# ABL_Covid_Test_UI_Module.net
KiCad netlist of a schematic drawn in EasyEDA
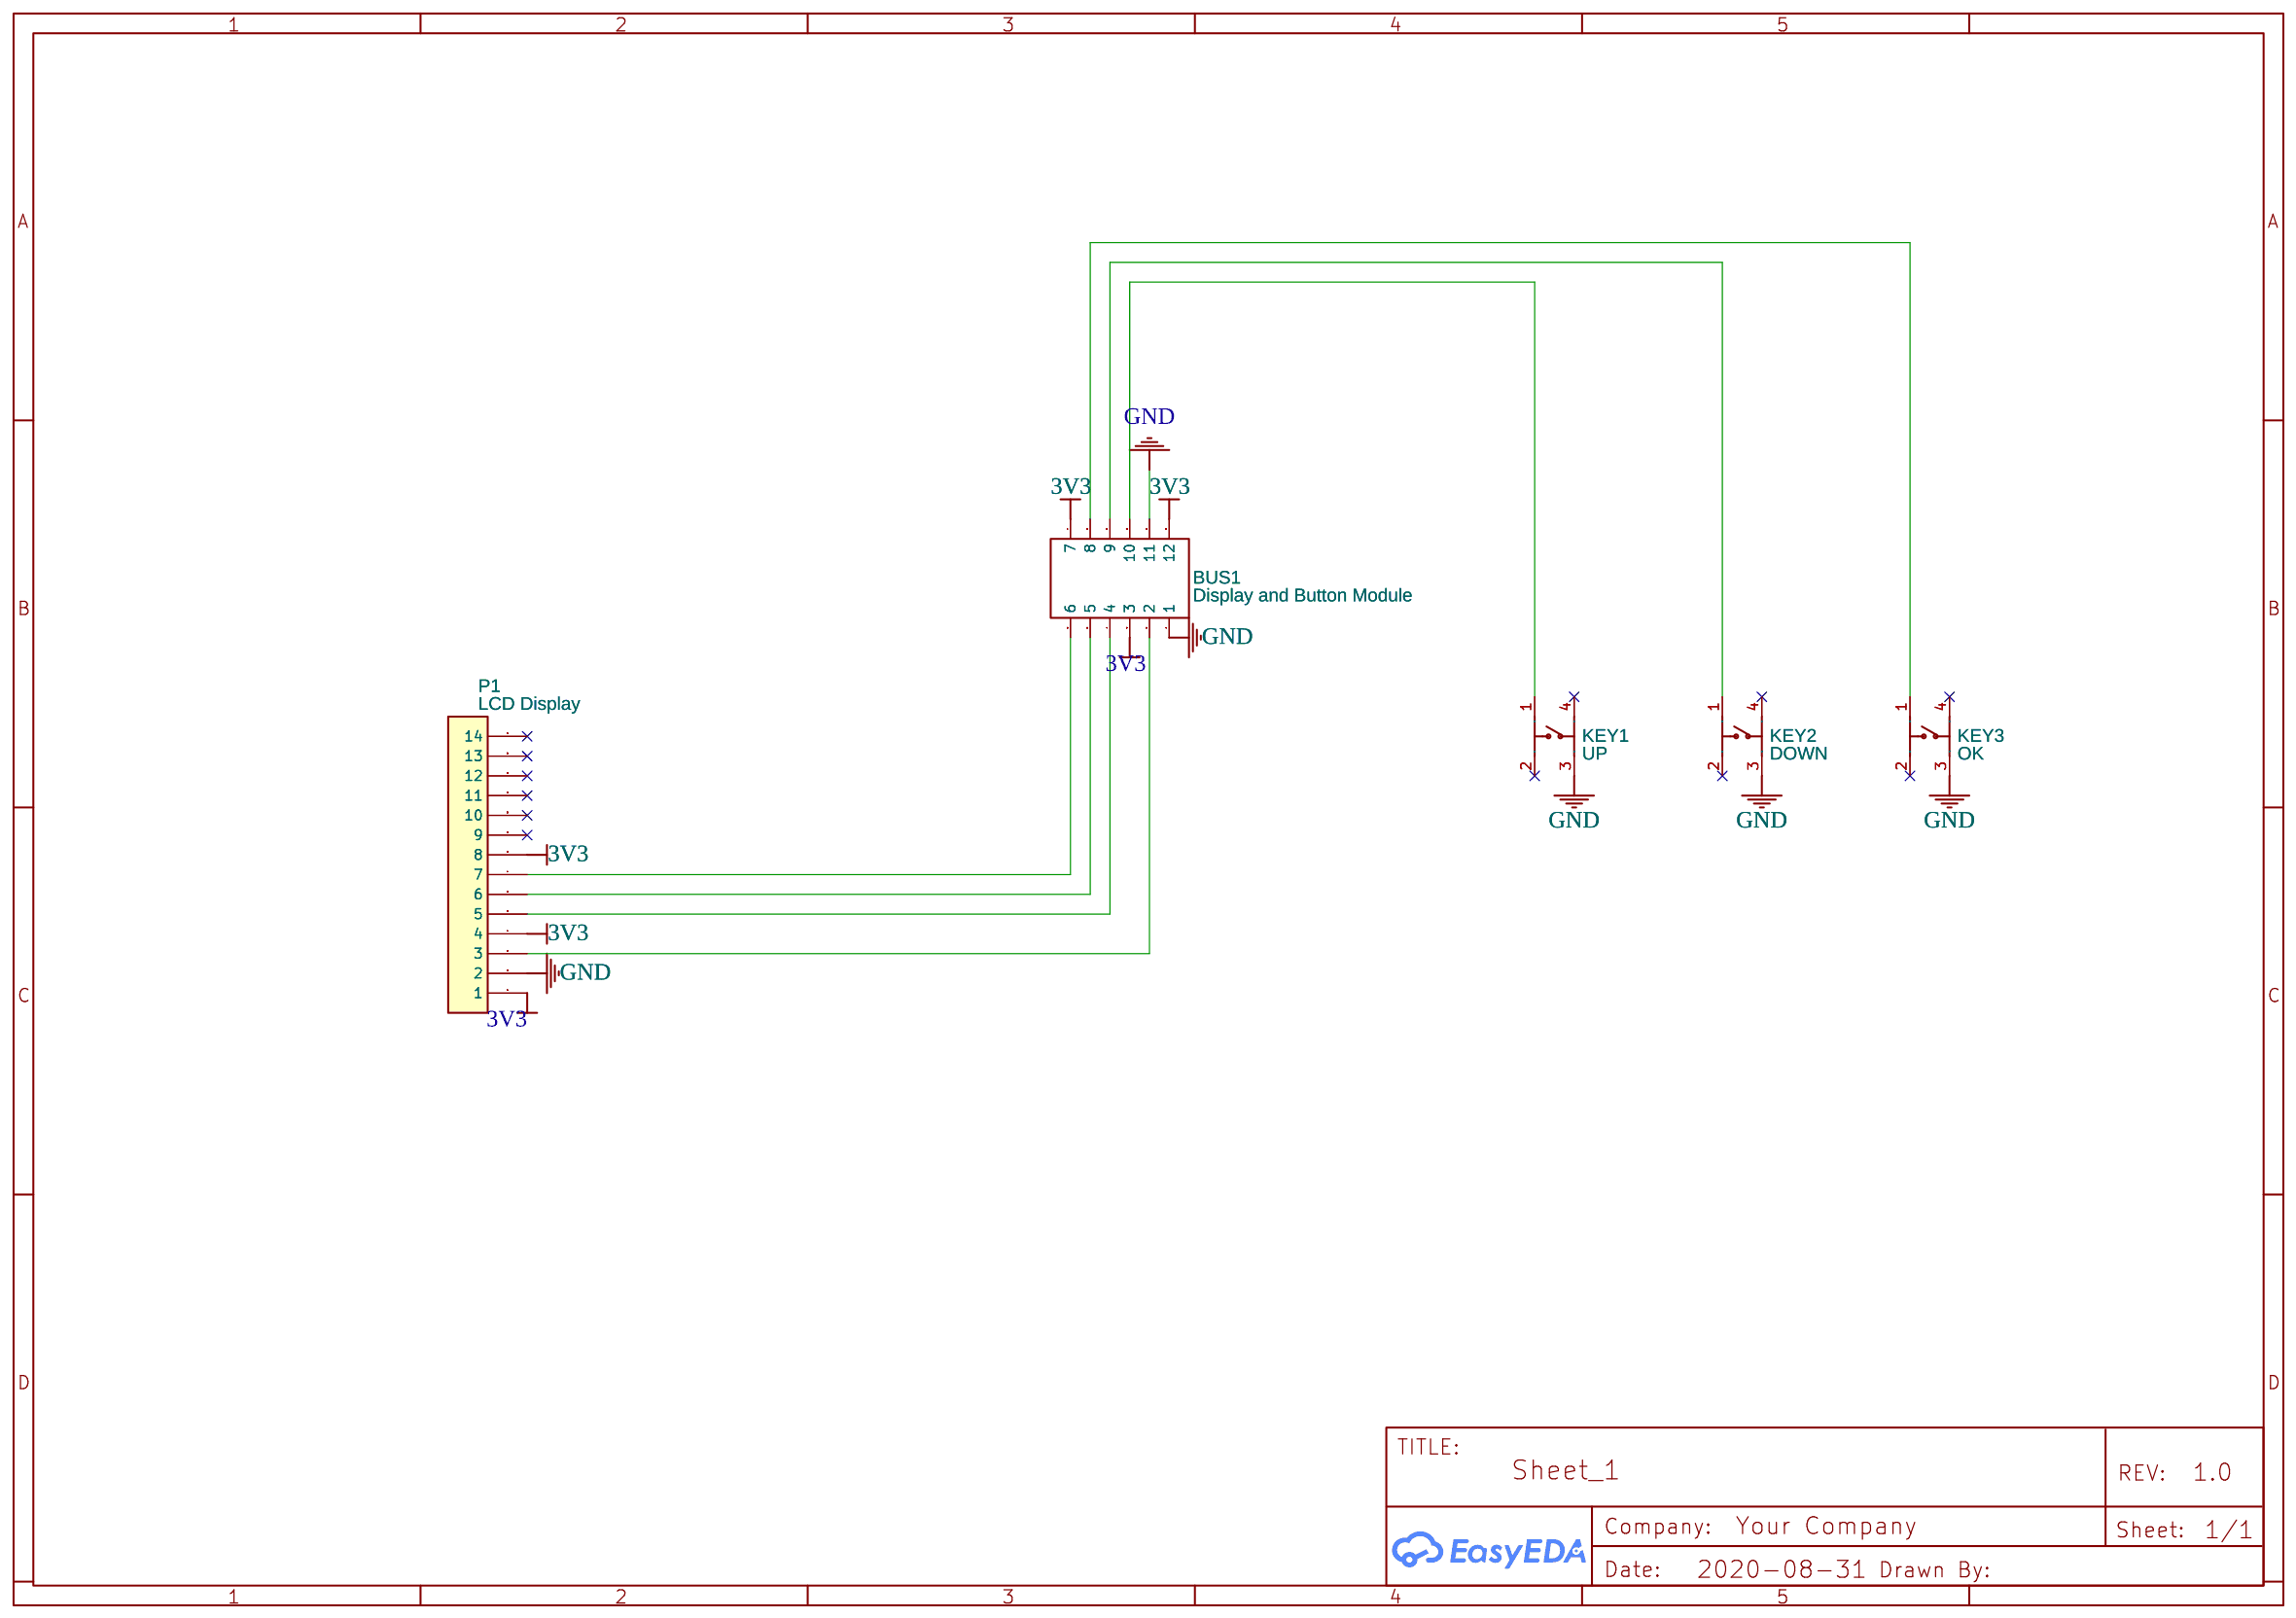
[diagram p0: schematic sheet]

(export (version "E")
  (design (tool "Eeschema 10.0.6"))
  (components
    (comp (ref "BUS1") (value "Display and Button Module") (libsource (lib "") (part "12p 2x6 header")))
    (comp (ref "KEY1")
      (value "UP")
      (fields
        (field (name "BOM_Manufacturer Part") "button6*6*8")
        (field (name "BOM_Supplier Part") "C59982")
      )
      (libsource (lib "") (part "button6*6*8"))
    )
    (comp (ref "KEY2")
      (value "DOWN")
      (fields
        (field (name "BOM_Manufacturer Part") "button6*6*8")
        (field (name "BOM_Supplier Part") "C59982")
      )
      (libsource (lib "") (part "button6*6*8"))
    )
    (comp (ref "KEY3")
      (value "OK")
      (fields
        (field (name "BOM_Manufacturer Part") "button6*6*8")
        (field (name "BOM_Supplier Part") "C59982")
      )
      (libsource (lib "") (part "button6*6*8"))
    )
    (comp (ref "P1") (value "LCD Display") (libsource (lib "") (part "HEADER 14X1")))
  )
  (nets
    (net (code "1") (name "3V3") (class "Default")
      (node (ref "BUS1") (pin "12") (pinfunction "12_12") (pintype "unspecified"))
      (node (ref "BUS1") (pin "3") (pinfunction "3_3") (pintype "unspecified"))
      (node (ref "BUS1") (pin "7") (pinfunction "7_7") (pintype "unspecified"))
      (node (ref "P1") (pin "1") (pinfunction "1_1") (pintype "unspecified"))
      (node (ref "P1") (pin "4") (pinfunction "4_4") (pintype "unspecified"))
      (node (ref "P1") (pin "8") (pinfunction "8_8") (pintype "unspecified"))
    )
    (net (code "2") (name "GND") (class "Default")
      (node (ref "BUS1") (pin "1") (pinfunction "1_1") (pintype "unspecified"))
      (node (ref "BUS1") (pin "11") (pinfunction "11_11") (pintype "unspecified"))
      (node (ref "KEY1") (pin "3") (pinfunction "3_3") (pintype "unspecified"))
      (node (ref "KEY2") (pin "3") (pinfunction "3_3") (pintype "unspecified"))
      (node (ref "KEY3") (pin "3") (pinfunction "3_3") (pintype "unspecified"))
      (node (ref "P1") (pin "2") (pinfunction "2_2") (pintype "unspecified"))
    )
    (net (code "3") (name "Net-(BUS1-Pad2)") (class "Default")
      (node (ref "BUS1") (pin "2") (pinfunction "2_2") (pintype "unspecified"))
      (node (ref "P1") (pin "3") (pinfunction "3_3") (pintype "unspecified"))
    )
    (net (code "4") (name "Net-(BUS1-Pad4)") (class "Default")
      (node (ref "BUS1") (pin "4") (pinfunction "4_4") (pintype "unspecified"))
      (node (ref "P1") (pin "5") (pinfunction "5_5") (pintype "unspecified"))
    )
    (net (code "5") (name "Net-(BUS1-Pad5)") (class "Default")
      (node (ref "BUS1") (pin "5") (pinfunction "5_5") (pintype "unspecified"))
      (node (ref "P1") (pin "6") (pinfunction "6_6") (pintype "unspecified"))
    )
    (net (code "6") (name "Net-(BUS1-Pad6)") (class "Default")
      (node (ref "BUS1") (pin "6") (pinfunction "6_6") (pintype "unspecified"))
      (node (ref "P1") (pin "7") (pinfunction "7_7") (pintype "unspecified"))
    )
    (net (code "7") (name "Net-(BUS1-Pad8)") (class "Default")
      (node (ref "BUS1") (pin "8") (pinfunction "8_8") (pintype "unspecified"))
      (node (ref "KEY3") (pin "1") (pinfunction "1_1") (pintype "unspecified"))
    )
    (net (code "8") (name "Net-(BUS1-Pad9)") (class "Default")
      (node (ref "BUS1") (pin "9") (pinfunction "9_9") (pintype "unspecified"))
      (node (ref "KEY2") (pin "1") (pinfunction "1_1") (pintype "unspecified"))
    )
    (net (code "9") (name "Net-(BUS1-Pad10)") (class "Default")
      (node (ref "BUS1") (pin "10") (pinfunction "10_10") (pintype "unspecified"))
      (node (ref "KEY1") (pin "1") (pinfunction "1_1") (pintype "unspecified"))
    )
    (net (code "10") (name "unconnected-(KEY1-Pad2)") (class "Default")
      (node (ref "KEY1") (pin "2") (pinfunction "2_2") (pintype "unspecified+no_connect"))
    )
    (net (code "11") (name "unconnected-(KEY1-Pad4)") (class "Default")
      (node (ref "KEY1") (pin "4") (pinfunction "4_4") (pintype "unspecified+no_connect"))
    )
    (net (code "12") (name "unconnected-(KEY2-Pad2)") (class "Default")
      (node (ref "KEY2") (pin "2") (pinfunction "2_2") (pintype "unspecified+no_connect"))
    )
    (net (code "13") (name "unconnected-(KEY2-Pad4)") (class "Default")
      (node (ref "KEY2") (pin "4") (pinfunction "4_4") (pintype "unspecified+no_connect"))
    )
    (net (code "14") (name "unconnected-(KEY3-Pad2)") (class "Default")
      (node (ref "KEY3") (pin "2") (pinfunction "2_2") (pintype "unspecified+no_connect"))
    )
    (net (code "15") (name "unconnected-(KEY3-Pad4)") (class "Default")
      (node (ref "KEY3") (pin "4") (pinfunction "4_4") (pintype "unspecified+no_connect"))
    )
    (net (code "16") (name "unconnected-(P1-Pad9)") (class "Default")
      (node (ref "P1") (pin "9") (pinfunction "9_9") (pintype "unspecified+no_connect"))
    )
    (net (code "17") (name "unconnected-(P1-Pad10)") (class "Default")
      (node (ref "P1") (pin "10") (pinfunction "10_10") (pintype "unspecified+no_connect"))
    )
    (net (code "18") (name "unconnected-(P1-Pad11)") (class "Default")
      (node (ref "P1") (pin "11") (pinfunction "11_11") (pintype "unspecified+no_connect"))
    )
    (net (code "19") (name "unconnected-(P1-Pad12)") (class "Default")
      (node (ref "P1") (pin "12") (pinfunction "12_12") (pintype "unspecified+no_connect"))
    )
    (net (code "20") (name "unconnected-(P1-Pad13)") (class "Default")
      (node (ref "P1") (pin "13") (pinfunction "13_13") (pintype "unspecified+no_connect"))
    )
    (net (code "21") (name "unconnected-(P1-Pad14)") (class "Default")
      (node (ref "P1") (pin "14") (pinfunction "14_14") (pintype "unspecified+no_connect"))
    )
  )
)
